# MAINSSMB_V1_2.net
KiCad netlist of a schematic drawn in Altium Designer
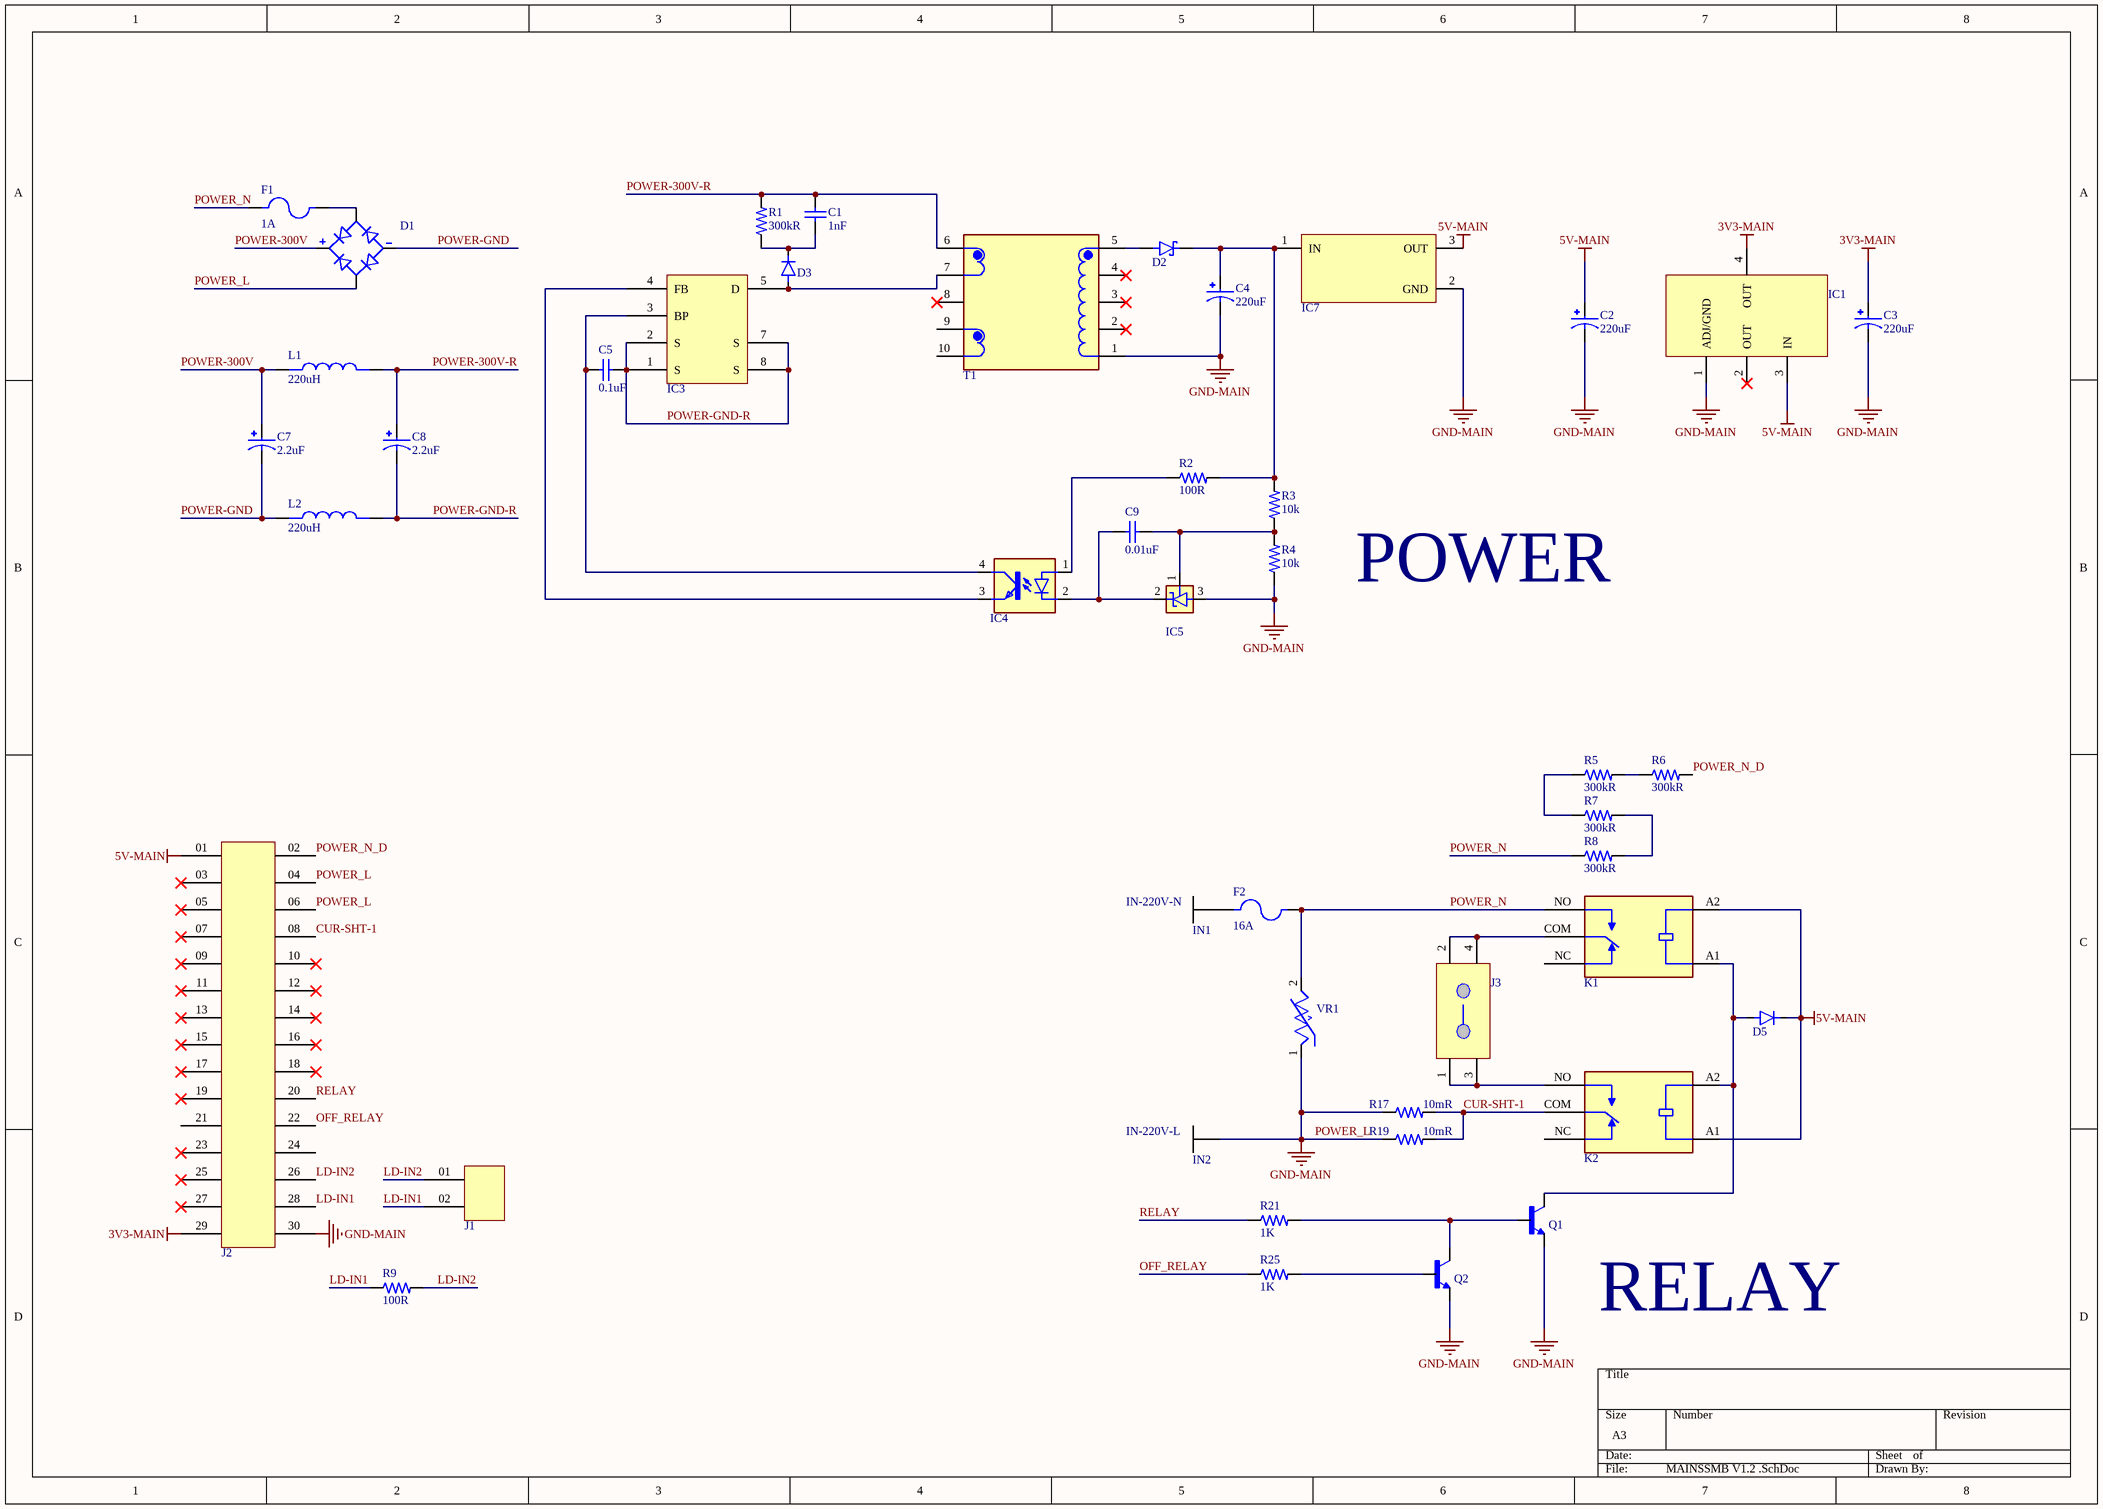
[diagram p0: MAINSSMB V1.2 .SchDoc]

(export (version "E")
  (design (tool "Eeschema 10.0.6"))
  (components
    (comp (ref "C1")
      (value "1nF")
      (footprint "TH-CAP-HxLxW-5.5x4.0x2.5-TDKC")
      (description "Capacitor Ceramic 0.001uF 50V C0G 5% 5mm T/R")
      (fields
        (field (name "MANUFACTURER") "TDK")
        (field (name "MANUFACTURER PART NUMBER") "FA28NP01H102JNU06")
        (field (name "DESIGNER") "TVBac")
      )
      (libsource (lib "Capacitors") (part "CAP; TH; 0.001uF; 50V; FA28NP01H102JNU06"))
    )
    (comp (ref "C2")
      (value "220uF")
      (footprint "SMD-DxLxW-6.3x6.6x6.6-PEC")
      (description "Cap Aluminum Polymer 220uF 16VDC 20% (6.3 X 5.9mm) SMD 0.022 Ohm 1040mA 1000h 125C T/R")
      (fields
        (field (name "MANUFACTURER") "Panasonic")
        (field (name "MANUFACTURER PART NUMBER") "16SVPK220M")
        (field (name "DESIGNER") "TVBac")
      )
      (libsource (lib "Capacitors") (part "CAP; 220uF; 16V; SMD; 16SVPK220M"))
    )
    (comp (ref "C3")
      (value "220uF")
      (footprint "SMD-DxLxW-6.3x6.6x6.6-PEC")
      (description "Cap Aluminum Polymer 220uF 10VDC 20%( 6.3 X 5.9mm) SMD 0.02 Ohm 2700mA 2000h 105C T/R")
      (fields
        (field (name "MANUFACTURER") "Panasonic")
        (field (name "MANUFACTURER PART NUMBER") "10SVPE220M")
        (field (name "DESIGNER") "TVBac")
      )
      (libsource (lib "Capacitors") (part "CAP; 220uF; 10V; SMD; 10SVPE220M"))
    )
    (comp (ref "C4")
      (value "220uF")
      (footprint "SMD-DxLxW-6.3x6.6x6.6-PEC")
      (description "Cap Aluminum Polymer 220uF 16VDC 20% (6.3 X 5.9mm) SMD 0.022 Ohm 1040mA 1000h 125C T/R")
      (fields
        (field (name "MANUFACTURER") "Panasonic")
        (field (name "MANUFACTURER PART NUMBER") "16SVPK220M")
        (field (name "DESIGNER") "TVBac")
      )
      (libsource (lib "Capacitors") (part "CAP; 220uF; 16V; SMD; 16SVPK220M"))
    )
    (comp (ref "C5")
      (value "0.1uF")
      (footprint "SMD-CAP-0603-YAGEO")
      (description "Multilayer Ceramic Capacitor, 0.1 uF, 50 V, ï¿½ 5%, X7R, 0603 [1608 Metric]")
      (fields
        (field (name "MANUFACTURER") "Yageo")
        (field (name "MANUFACTURER PART NUMBER") "CC0603JRX7R9BB104")
        (field (name "DESIGNER") "TVBac")
      )
      (libsource (lib "Capacitors") (part "CAP; 0.1uF; 50V; 0603; SMD; CC0603JRX7R9BB104"))
    )
    (comp (ref "C7")
      (value "2.2uF")
      (footprint "TH-CAP-HxD-12.5x8.0-PEC")
      (description "Cap Aluminum Lytic 2.2uF 400V 20% (8 X 11.5mm) Radial 3.5mm 50mA 2000h 85C Automotive Bulk")
      (fields
        (field (name "MANUFACTURER") "Panasonic")
        (field (name "MANUFACTURER PART NUMBER") "ECA-2GM2R2")
        (field (name "DESIGNER") "TVBac")
      )
      (libsource (lib "Capacitors") (part "CAP; TH; 2.2uF; 400V; ECA-2GM2R2"))
    )
    (comp (ref "C8")
      (value "2.2uF")
      (footprint "TH-CAP-HxD-12.5x8.0-PEC")
      (description "Cap Aluminum Lytic 2.2uF 400V 20% (8 X 11.5mm) Radial 3.5mm 50mA 2000h 85C Automotive Bulk")
      (fields
        (field (name "MANUFACTURER") "Panasonic")
        (field (name "MANUFACTURER PART NUMBER") "ECA-2GM2R2")
        (field (name "DESIGNER") "TVBac")
      )
      (libsource (lib "Capacitors") (part "CAP; TH; 2.2uF; 400V; ECA-2GM2R2"))
    )
    (comp (ref "C9")
      (value "0.01uF")
      (footprint "SMD-CAP-0603-YAGEO")
      (description "Surface Mount Ceramic Multilayer Capacitor 0.01uF 5% X7R 25V 0603 Paper T/R")
      (fields
        (field (name "MANUFACTURER") "Yageo")
        (field (name "MANUFACTURER PART NUMBER") "CC0603JRX7R8BB103")
        (field (name "DESIGNER") "TVBac")
      )
      (libsource (lib "Capacitors") (part "CAP; 0.01uF; 25V; 0603; SMD; CC0603JRX7R8BB103"))
    )
    (comp (ref "D1")
      (value "Bridge Rectifier Single Phase Standard 1 kV Surface Mount ABS")
      (footprint "DIODE-SMD-4-TSC")
      (description "Bridge Rectifiers 1A, 1000V, Standard Bridge Rectifier")
      (fields
        (field (name "MANUFACTURER") "Taiwan Semiconductor")
        (field (name "MANUFACTURER PART NUMBER") "ABS10H")
        (field (name "DESIGNER") "TVBac")
      )
      (libsource (lib "Diode") (part "DIODE; SMD; ABS10H"))
    )
    (comp (ref "D2")
      (value "Diode 40 V 3A Surface Mount DO-214AC (SMA)")
      (footprint "SMD-DO-214AC-214-CT")
      (description "Diode Schottky Si 40V 3A 2-Pin SMA T/R")
      (fields
        (field (name "MANUFACTURER") "Comchip")
        (field (name "MANUFACTURER PART NUMBER") "SS34-HF")
        (field (name "DESIGNER") "TVBac")
      )
      (libsource (lib "Smartsocket") (part "DIODE; SMD; SCHOTTKY; SS34-HF"))
    )
    (comp (ref "D3")
      (value "Diode 1000 V 1A Surface Mount SOD-123FL")
      (footprint "SOD-123FL-SMCDS")
      (description "Diode Gen Purp 1KV 1A SOD123FL")
      (fields
        (field (name "MANUFACTURER") "Sangdest Microelectronics")
        (field (name "MANUFACTURER PART NUMBER") "1N4007FL")
        (field (name "DESIGNER") "TVBac")
      )
      (libsource (lib "Diode") (part "DIODE; SMD; 1N4007FLN4007;"))
    )
    (comp (ref "D5")
      (value "Diode 1000 V 1A Surface Mount SOD-123FL")
      (footprint "SOD-123FL-SMCDS")
      (description "Diode Gen Purp 1KV 1A SOD123FL")
      (fields
        (field (name "MANUFACTURER") "Sangdest Microelectronics")
        (field (name "MANUFACTURER PART NUMBER") "1N4007FL")
        (field (name "DESIGNER") "TVBac")
      )
      (libsource (lib "Diode") (part "DIODE; SMD; 1N4007FLN4007;"))
    )
    (comp (ref "F1")
      (value "1A")
      (footprint "FUSE-HxLxW-8.0x8.5x4.0-LI")
      (description "Fuse Subminiature Slow Blow Acting 1A 300V Radial 8.5 X 4 X 8mm Ammo Pack")
      (fields
        (field (name "MANUFACTURER") "Littelfuse Wickmann")
        (field (name "MANUFACTURER PART NUMBER") "36911000000")
        (field (name "DESIGNER") "TVBac")
      )
      (libsource (lib "Smartsocket") (part "FUSE; 1A; 36911000000"))
    )
    (comp (ref "F2")
      (value "16A")
      (footprint "FUSE-3.6mmx10mm-AXIAL")
      (fields
        (field (name "MANUFACTURER") "Schurter")
        (field (name "MANUFACTURER PART NUMBER") "0031.8211")
        (field (name "Comment") "FUSE; 16A; 0031.8211_1")
        (field (name "DESIGNER") "TVBac")
      )
      (libsource (lib "Socket") (part "FUSE; 16A; 0031.8211_1"))
    )
    (comp (ref "IC1")
      (value "Linear Voltage Regulator IC Positive Fixed 1 Output 1A SOT-223-3")
      (footprint "IC:SOT-223-3-DI")
      (description "Linear Voltage Regulator IC 1 Output 1A SOT-223")
      (fields
        (field (name "MF") "Diodes Inc.")
        (field (name "MP") "AZ1117EH-3.3TRG1")
        (field (name "DESIGNER") "TVBac")
      )
      (libsource (lib "IC") (part "LDO; 3V3; 1A; SMD; AZ1117EH-3.3TRG1"))
    )
    (comp (ref "IC3")
      (value "Converter Offline Flyback Topology 132kHz SMD-8B")
      (footprint "SMD-8B-PI")
      (description "AC to DC Switching Converter Off-Line Switcher 140kHz 7-Pin SMD-B / IC OFFLINE SWIT HV 8SMD")
      (fields
        (field (name "MANUFACTURER") "Power Integrations")
        (field (name "MANUFACTURER PART NUMBER") "LNK364GN-TL")
        (field (name "DESIGNER") "TVBac")
      )
      (libsource (lib "Smartsocket") (part "LNK364GN-TL"))
    )
    (comp (ref "IC4")
      (value "Optoisolator Transistor Output 3750Vrms 1 Channel 4-SOP (2.54mm)")
      (footprint "SOP-4")
      (description "Transistor Output Optocoupler, 1-Element, 3750V Isolation")
      (fields (field (name "MANUFACTURER") "Everlight") (field (name "MANUFACTURER PART NUMBER") "EL357N-G"))
      (libsource (lib "IC") (part "ISO; 1CH; EL357N-G"))
    )
    (comp (ref "IC5")
      (value "Shunt Voltage Reference IC Adjustable 2.495V 36 VV ±1% 100 mA SOT-23-3")
      (footprint "SOT-23-3-DS")
      (description "V-Ref Adjustable 2.495V to 36V 100mA Automotive 3-Pin SOT-23 T/R")
      (fields
        (field (name "MANUFACTURER") "Texas Instruments")
        (field (name "MANUFACTURER PART NUMBER") "TL431AIDBZR")
        (field (name "DESIGNER") "TVBac")
      )
      (libsource (lib "IC") (part "TL431AIDBZR; MIRROID;"))
    )
    (comp (ref "IC7")
      (value "Linear Voltage Regulator IC Positive Fixed 1 Output 1A TO-252")
      (footprint "TO252-3-RS")
      (description "Linear Voltage Regulator, Fixed, Positive Output, 7.5 V to 25 V, 5V, 1A, 3 Pins, TO-252 (DPAK)")
      (fields
        (field (name "MANUFACTURER") "Rohm")
        (field (name "MANUFACTURER PART NUMBER") "BA17805FP-E2")
        (field (name "DESIGNER") "TVBac")
      )
      (libsource (lib "IC") (part "LDO; 5V; 1A; BA17805FP-E2"))
    )
    (comp (ref "IN1")
      (value "INPUT")
      (footprint "INPUT-2.0x3.5")
      (fields (field (name "DESIGNER") "TVBac"))
      (libsource (lib "Socket") (part "INPUT-2.0x3.5"))
    )
    (comp (ref "IN2")
      (value "INPUT")
      (footprint "INPUT-2.0x3.5")
      (fields (field (name "DESIGNER") "TVBac"))
      (libsource (lib "Socket") (part "INPUT-2.0x3.5"))
    )
    (comp (ref "J1")
      (value "Connector Header Through Hole 2 position")
      (footprint "HEADER-2.54-2")
      (description "Headers & Wire Housings Classic PCB Header Strips, 0.100 pitch")
      (fields
        (field (name "MANUFACTURER") "Samtec")
        (field (name "MANUFACTURER PART NUMBER") "TSW-101-15-T-D")
        (field (name "DESIGNER") "TVBac")
      )
      (libsource (lib "Socket") (part "HEADER; 2PIN; 2.54; VER; TSW-101-15-T-D"))
    )
    (comp (ref "J2")
      (value "30 Position Elevated Socket Connector 0.100\" (2.54mm) Through Hole Gold")
      (footprint "HEADER-2.54-15x2-HOR-SAM - N3D")
      (description "Connector Receptacle 30 Position 0.100\" (2.54mm) Gold Through Hole")
      (fields
        (field (name "MANUFACTURER") "Samtec")
        (field (name "MANUFACTURER PART NUMBER") "ESQ-115-12-G-D")
        (field (name "DESIGNER") "TVBac")
      )
      (libsource (lib "Socket") (part "HEADER; 15x2PIN; 2.54; VER; ESQ-115-12-G-D; N3D"))
    )
    (comp (ref "J3")
      (value "Connector Header Through Hole 4 position 0.100\" (2.54mm)")
      (footprint "SOCKET-SINGLE-WEV1081H")
      (description "Conn Unshrouded Header HDR 4 POS 2.54mm Solder ST Thru-Hole Automotive Bulk")
      (fields
        (field (name "MANUFACTURER") "Samtec")
        (field (name "MANUFACTURER PART NUMBER") "TSW-104-14-L-S")
        (field (name "DESIGNER") "TVBac")
      )
      (libsource (lib "Socket") (part "SOCKET; SINGLE;"))
    )
    (comp (ref "K1")
      (value "JQ1P-5V-F")
      (footprint "RELAY-JQ1P-10A-HxLxW-15.6x20.5x10.0-PEW")
      (description "RELAY GEN PURPOSE SPDT 10A 5V")
      (fields (field (name "DESIGNER") "TVBac"))
      (libsource (lib "Relay") (part "RELAY; SINGLE; 5VDC; CMP-05607-000163-1"))
    )
    (comp (ref "K2")
      (value "JQ1P-5V-F")
      (footprint "RELAY-JQ1P-10A-HxLxW-15.6x20.5x10.0-PEW")
      (description "RELAY GEN PURPOSE SPDT 10A 5V")
      (fields (field (name "DESIGNER") "TVBac"))
      (libsource (lib "Relay") (part "RELAY; SINGLE; 5VDC; CMP-05607-000163-1"))
    )
    (comp (ref "L1")
      (value "220uH")
      (footprint "SMD-HxLxW-1.8x4.0x4.0-ALLC")
      (description "Power Inductor (SMD), 220 uH, ± 20%, 250 mA, Shielded, 330 mA, 4mm x 4mm x 1.8mm")
      (fields
        (field (name "MANUFACTURER") "Abracon")
        (field (name "MANUFACTURER PART NUMBER") "ASPI-0418FS-221M-T3")
        (field (name "DESIGNER") "TVBac")
      )
      (libsource (lib "Inductors") (part "IND; 220uH; 250mA; ASPI-0418FS-221M-T3"))
    )
    (comp (ref "L2")
      (value "220uH")
      (footprint "SMD-HxLxW-1.8x4.0x4.0-ALLC")
      (description "Power Inductor (SMD), 220 uH, ± 20%, 250 mA, Shielded, 330 mA, 4mm x 4mm x 1.8mm")
      (fields
        (field (name "MANUFACTURER") "Abracon")
        (field (name "MANUFACTURER PART NUMBER") "ASPI-0418FS-221M-T3")
        (field (name "DESIGNER") "TVBac")
      )
      (libsource (lib "Inductors") (part "IND; 220uH; 250mA; ASPI-0418FS-221M-T3"))
    )
    (comp (ref "Q1")
      (value "Bipolar (BJT) Transistor NPN 45 V 500 mA 100MHz 300 mW Surface Mount SOT-23-3 (TO-236)")
      (footprint "SOT-23-3-ONSEMI")
      (description "Single Bipolar Transistor, NPN, 45 V, 500 mA, 225 mW, SOT-23 (TO-236), 3 Pins, Surface Mount")
      (fields
        (field (name "MANUFACTURER") "ON Semiconductor")
        (field (name "MANUFACTURER PART NUMBER") "BC817-25LT1G")
        (field (name "DESIGNER") "TVBac")
      )
      (libsource (lib "Transistors") (part "TRAN; NPN; 500mA;V;  BC817-25LT1G"))
    )
    (comp (ref "Q2")
      (value "Bipolar (BJT) Transistor NPN 45 V 500 mA 100MHz 300 mW Surface Mount SOT-23-3 (TO-236)")
      (footprint "SOT-23-3-ONSEMI")
      (description "Single Bipolar Transistor, NPN, 45 V, 500 mA, 225 mW, SOT-23 (TO-236), 3 Pins, Surface Mount")
      (fields
        (field (name "MANUFACTURER") "ON Semiconductor")
        (field (name "MANUFACTURER PART NUMBER") "BC817-25LT1G")
        (field (name "DESIGNER") "TVBac")
      )
      (libsource (lib "Transistors") (part "TRAN; NPN; 500mA;V;  BC817-25LT1G"))
    )
    (comp (ref "R1")
      (value "300kR")
      (footprint "SMD-RES-1206-RS")
      (description "Res Thick Film 1206 300K Ohm 1% 0.5W(1/2W) ±100ppm/C Epoxy Resin Pad SMD Automotive T/R")
      (fields
        (field (name "MANUFACTURER") "Rohm")
        (field (name "MANUFACTURER PART NUMBER") "ESR18EZPF3003")
        (field (name "DESIGNER") "TVBac")
      )
      (libsource (lib "Resistors") (part "RES; 300K; 1206; ESR18EZPF3003"))
    )
    (comp (ref "R2")
      (value "100R")
      (footprint "SMD-RES-0603-RS")
      (description "Res Thick Film 0603 100 Ohm 1% 0.1W(1/10W) ±100ppm/C Pad SMD T/R Automotive AEC-Q200")
      (fields
        (field (name "MANUFACTURER") "Rohm")
        (field (name "MANUFACTURER PART NUMBER") "KTR03EZPF1000")
        (field (name "DESIGNER") "TVBac")
      )
      (libsource (lib "Resistors") (part "RES; 100R; 0603; SMD; KTR03EZPF1000"))
    )
    (comp (ref "R3")
      (value "10k")
      (footprint "SMD-RES-0603-SEI")
      (description "SMD Chip Resistor, 10 kOhm, ± 1%, 250 mW, 0603 [1608 Metric], Thick Film, Anti-Surge")
      (fields
        (field (name "MANUFACTURER") "Rohm")
        (field (name "MANUFACTURER PART NUMBER") "ESR03EZPF1002")
        (field (name "DESIGNER") "TVBac")
      )
      (libsource (lib "Resistors") (part "RES; 10K; 0603; SMD; ESR03EZPF1002"))
    )
    (comp (ref "R4")
      (value "10k")
      (footprint "SMD-RES-0603-SEI")
      (description "SMD Chip Resistor, 10 kOhm, ± 1%, 250 mW, 0603 [1608 Metric], Thick Film, Anti-Surge")
      (fields
        (field (name "MANUFACTURER") "Rohm")
        (field (name "MANUFACTURER PART NUMBER") "ESR03EZPF1002")
        (field (name "DESIGNER") "TVBac")
      )
      (libsource (lib "Resistors") (part "RES; 10K; 0603; SMD; ESR03EZPF1002"))
    )
    (comp (ref "R5")
      (value "300kR")
      (footprint "SMD-RES-0603-RS")
      (description "Res High Voltage Thick Film 0603 300k Ohm 1% 1/10W ±100ppm/°C Molded Paper T/R")
      (fields
        (field (name "MANUFACTURER") "Rohm")
        (field (name "MANUFACTURER PART NUMBER") "KTR03EZPF3003")
        (field (name "DESIGNER") "TVBac")
      )
      (libsource (lib "Resistors") (part "RES; 300K; 0603; SMD; KTR03EZPF3003"))
    )
    (comp (ref "R6")
      (value "300kR")
      (footprint "SMD-RES-0603-RS")
      (description "Res High Voltage Thick Film 0603 300k Ohm 1% 1/10W ±100ppm/°C Molded Paper T/R")
      (fields
        (field (name "MANUFACTURER") "Rohm")
        (field (name "MANUFACTURER PART NUMBER") "KTR03EZPF3003")
        (field (name "DESIGNER") "TVBac")
      )
      (libsource (lib "Resistors") (part "RES; 300K; 0603; SMD; KTR03EZPF3003"))
    )
    (comp (ref "R7")
      (value "300kR")
      (footprint "SMD-RES-0603-RS")
      (description "Res High Voltage Thick Film 0603 300k Ohm 1% 1/10W ±100ppm/°C Molded Paper T/R")
      (fields
        (field (name "MANUFACTURER") "Rohm")
        (field (name "MANUFACTURER PART NUMBER") "KTR03EZPF3003")
        (field (name "DESIGNER") "TVBac")
      )
      (libsource (lib "Resistors") (part "RES; 300K; 0603; SMD; KTR03EZPF3003"))
    )
    (comp (ref "R8")
      (value "300kR")
      (footprint "SMD-RES-0603-RS")
      (description "Res High Voltage Thick Film 0603 300k Ohm 1% 1/10W ±100ppm/°C Molded Paper T/R")
      (fields
        (field (name "MANUFACTURER") "Rohm")
        (field (name "MANUFACTURER PART NUMBER") "KTR03EZPF3003")
        (field (name "DESIGNER") "TVBac")
      )
      (libsource (lib "Resistors") (part "RES; 300K; 0603; SMD; KTR03EZPF3003"))
    )
    (comp (ref "R9")
      (value "100R")
      (footprint "SMD-RES-0603-RS")
      (description "Res Thick Film 0603 100 Ohm 1% 0.1W(1/10W) ±100ppm/C Pad SMD T/R Automotive AEC-Q200")
      (fields
        (field (name "MANUFACTURER") "Rohm")
        (field (name "MANUFACTURER PART NUMBER") "KTR03EZPF1000")
        (field (name "DESIGNER") "TVBac")
      )
      (libsource (lib "Resistors") (part "RES; 100R; 0603; SMD; KTR03EZPF1000"))
    )
    (comp (ref "R17")
      (value "10mR")
      (footprint "SMD-RES-2512-VD")
      (description "Res Current Sense Metal Plate 2512 0.01 Ohm 1% 3W ±110ppm/°C Molded T/R")
      (fields
        (field (name "MANUFACTURER") "Vishay")
        (field (name "MANUFACTURER PART NUMBER") "WFMA2512R0100FEA")
        (field (name "DESIGNER") "TVBac")
      )
      (libsource (lib "Smartsocket") (part "RES; SHUNT; 10mOhm; SMD; WFMA2512R0100FEA"))
    )
    (comp (ref "R19")
      (value "10mR")
      (footprint "SMD-RES-2512-VD")
      (description "Res Current Sense Metal Plate 2512 0.01 Ohm 1% 3W ±110ppm/°C Molded T/R")
      (fields
        (field (name "MANUFACTURER") "Vishay")
        (field (name "MANUFACTURER PART NUMBER") "WFMA2512R0100FEA")
        (field (name "DESIGNER") "TVBac")
      )
      (libsource (lib "Smartsocket") (part "RES; SHUNT; 10mOhm; SMD; WFMA2512R0100FEA"))
    )
    (comp (ref "R21")
      (value "1K")
      (footprint "SMD-RES-0603-SEI")
      (description "SMD Chip Resistor, 1 kOhm, ± 1%, 250 mW, 0603 [1608 Metric], Thick Film, Anti-Surge")
      (fields
        (field (name "MANUFACTURER") "Rohm")
        (field (name "MANUFACTURER PART NUMBER") "ESR03EZPF1001")
        (field (name "DESIGNER") "TVBac")
      )
      (libsource (lib "Smartsocket") (part "RES; 1K; 0603; SMD; ESR03EZPF1001"))
    )
    (comp (ref "R25")
      (value "1K")
      (footprint "SMD-RES-0603-SEI")
      (description "SMD Chip Resistor, 1 kOhm, ± 1%, 250 mW, 0603 [1608 Metric], Thick Film, Anti-Surge")
      (fields
        (field (name "MANUFACTURER") "Rohm")
        (field (name "MANUFACTURER PART NUMBER") "ESR03EZPF1001")
        (field (name "DESIGNER") "TVBac")
      )
      (libsource (lib "Smartsocket") (part "RES; 1K; 0603; SMD; ESR03EZPF1001"))
    )
    (comp (ref "T1")
      (value "For SMPS Transformer 500VAC Isolation Through Hole")
      (footprint "EE13 - POWER")
      (description "OFFLINE TRANSFORMER 6W EE13/7/6")
      (fields (field (name "MF") "Wurth Electronics Inc") (field (name "MP") "EE13/6/6"))
      (libsource (lib "Transformer") (part "EE13/6/6-Power"))
    )
    (comp (ref "VR1")
      (value "VAR; B72214S0271K101")
      (footprint "VARISTOR-TDK")
      (description "Var MOV 275VAC/350VDC 4500A 430V Thru-Hole Radial Automotive Bulk")
      (fields
        (field (name "MANUFACTURER") "TDK EPCOS")
        (field (name "MANUFACTURER PART NUMBER") "B72214S0271K101")
      )
      (libsource (lib "Capacitors") (part "VAR; B72214S0271K101"))
    )
  )
  (nets
    (net (code "1") (name "/CUR-SHT-1") (class "Default")
      (node (ref "J2") (pin "08") (pinfunction "08_08") (pintype "passive"))
      (node (ref "K2") (pin "COM") (pinfunction "COM_COM") (pintype "passive"))
      (node (ref "R17") (pin "2") (pinfunction "2_2") (pintype "passive"))
      (node (ref "R19") (pin "2") (pinfunction "2_2") (pintype "passive"))
    )
    (net (code "2") (name "/LD-IN1") (class "Default")
      (node (ref "J1") (pin "02") (pinfunction "2_02") (pintype "passive"))
      (node (ref "J2") (pin "28") (pinfunction "28_28") (pintype "passive"))
      (node (ref "R9") (pin "1") (pinfunction "1_1") (pintype "passive"))
    )
    (net (code "3") (name "/LD-IN2") (class "Default")
      (node (ref "J1") (pin "01") (pinfunction "1_01") (pintype "passive"))
      (node (ref "J2") (pin "26") (pinfunction "26_26") (pintype "passive"))
      (node (ref "R9") (pin "2") (pinfunction "2_2") (pintype "passive"))
    )
    (net (code "4") (name "/OFF_RELAY") (class "Default")
      (node (ref "J2") (pin "22") (pinfunction "22_22") (pintype "passive"))
      (node (ref "R25") (pin "1") (pinfunction "1_1") (pintype "passive"))
    )
    (net (code "5") (name "/POWER-300V") (class "Default")
      (node (ref "C7") (pin "1") (pinfunction "1_1") (pintype "passive"))
      (node (ref "D1") (pin "POS") (pinfunction "POS_POS") (pintype "passive"))
      (node (ref "L1") (pin "1") (pinfunction "1_1") (pintype "passive"))
    )
    (net (code "6") (name "/POWER-300V-R") (class "Default")
      (node (ref "C1") (pin "2") (pinfunction "2_2") (pintype "passive"))
      (node (ref "C8") (pin "1") (pinfunction "1_1") (pintype "passive"))
      (node (ref "L1") (pin "2") (pinfunction "2_2") (pintype "passive"))
      (node (ref "R1") (pin "2") (pinfunction "2_2") (pintype "passive"))
      (node (ref "T1") (pin "6") (pinfunction "6_6") (pintype "passive"))
    )
    (net (code "7") (name "/POWER-GND") (class "Default")
      (node (ref "C7") (pin "2") (pinfunction "2_2") (pintype "passive"))
      (node (ref "D1") (pin "NEG") (pinfunction "NEG_NEG") (pintype "passive"))
      (node (ref "L2") (pin "1") (pinfunction "1_1") (pintype "passive"))
    )
    (net (code "8") (name "/POWER-GND-R") (class "Default")
      (node (ref "C5") (pin "2") (pinfunction "2_2") (pintype "passive"))
      (node (ref "C8") (pin "2") (pinfunction "2_2") (pintype "passive"))
      (node (ref "IC3") (pin "1") (pinfunction "S_1") (pintype "passive"))
      (node (ref "IC3") (pin "2") (pinfunction "S_2") (pintype "passive"))
      (node (ref "IC3") (pin "7") (pinfunction "S_7") (pintype "passive"))
      (node (ref "IC3") (pin "8") (pinfunction "S_8") (pintype "passive"))
      (node (ref "L2") (pin "2") (pinfunction "2_2") (pintype "passive"))
    )
    (net (code "9") (name "/POWER_N") (class "Default")
      (node (ref "F1") (pin "1") (pinfunction "1_1") (pintype "passive"))
      (node (ref "F2") (pin "2") (pinfunction "2_2") (pintype "passive"))
      (node (ref "K1") (pin "NO") (pinfunction "NO_NO") (pintype "passive"))
      (node (ref "R8") (pin "1") (pinfunction "1_1") (pintype "passive"))
      (node (ref "VR1") (pin "2") (pinfunction "2_2") (pintype "passive"))
    )
    (net (code "10") (name "/POWER_N_D") (class "Default")
      (node (ref "J2") (pin "02") (pinfunction "02_02") (pintype "passive"))
      (node (ref "R6") (pin "2") (pinfunction "2_2") (pintype "passive"))
    )
    (net (code "11") (name "/RELAY") (class "Default")
      (node (ref "J2") (pin "20") (pinfunction "20_20") (pintype "passive"))
      (node (ref "R21") (pin "1") (pinfunction "1_1") (pintype "passive"))
    )
    (net (code "12") (name "3V3-MAIN") (class "Default")
      (node (ref "C3") (pin "1") (pinfunction "1_1") (pintype "passive"))
      (node (ref "IC1") (pin "4") (pinfunction "OUT_4") (pintype "passive"))
      (node (ref "J2") (pin "29") (pinfunction "29_29") (pintype "passive"))
    )
    (net (code "13") (name "5V-MAIN") (class "Default")
      (node (ref "C2") (pin "1") (pinfunction "1_1") (pintype "passive"))
      (node (ref "D5") (pin "K") (pinfunction "K_K") (pintype "passive"))
      (node (ref "IC1") (pin "3") (pinfunction "IN_3") (pintype "passive"))
      (node (ref "IC7") (pin "3") (pinfunction "OUT_3") (pintype "passive"))
      (node (ref "J2") (pin "01") (pinfunction "01_01") (pintype "passive"))
      (node (ref "K1") (pin "A2") (pinfunction "A2_A2") (pintype "passive"))
      (node (ref "K2") (pin "A1") (pinfunction "A1_A1") (pintype "passive"))
    )
    (net (code "14") (name "GND-MAIN") (class "Default")
      (node (ref "C2") (pin "2") (pinfunction "2_2") (pintype "passive"))
      (node (ref "C3") (pin "2") (pinfunction "2_2") (pintype "passive"))
      (node (ref "C4") (pin "2") (pinfunction "2_2") (pintype "passive"))
      (node (ref "D1") (pin "AC2") (pinfunction "AC2_AC2") (pintype "passive"))
      (node (ref "IC1") (pin "1") (pinfunction "ADJ/GND_1") (pintype "passive"))
      (node (ref "IC5") (pin "3") (pinfunction "ANODE_3") (pintype "passive"))
      (node (ref "IC7") (pin "2") (pinfunction "GND_2") (pintype "passive"))
      (node (ref "IN2") (pin "1") (pinfunction "IN_1") (pintype "passive"))
      (node (ref "J2") (pin "04") (pinfunction "04_04") (pintype "passive"))
      (node (ref "J2") (pin "06") (pinfunction "06_06") (pintype "passive"))
      (node (ref "J2") (pin "30") (pinfunction "30_30") (pintype "passive"))
      (node (ref "Q1") (pin "2") (pinfunction "E_2") (pintype "passive"))
      (node (ref "Q2") (pin "2") (pinfunction "E_2") (pintype "passive"))
      (node (ref "R17") (pin "1") (pinfunction "1_1") (pintype "passive"))
      (node (ref "R19") (pin "1") (pinfunction "1_1") (pintype "passive"))
      (node (ref "R4") (pin "1") (pinfunction "1_1") (pintype "passive"))
      (node (ref "T1") (pin "1") (pinfunction "1_1") (pintype "passive"))
      (node (ref "VR1") (pin "1") (pinfunction "1_1") (pintype "passive"))
    )
    (net (code "15") (name "Net-(C1-Pad1)") (class "Default")
      (node (ref "C1") (pin "1") (pinfunction "1_1") (pintype "passive"))
      (node (ref "D3") (pin "K") (pinfunction "K_K") (pintype "passive"))
      (node (ref "R1") (pin "1") (pinfunction "1_1") (pintype "passive"))
    )
    (net (code "16") (name "Net-(D1-PadAC1)") (class "Default")
      (node (ref "D1") (pin "AC1") (pinfunction "AC1_AC1") (pintype "passive"))
      (node (ref "F1") (pin "2") (pinfunction "2_2") (pintype "passive"))
    )
    (net (code "17") (name "Net-(D2-A)") (class "Default")
      (node (ref "D2") (pin "2") (pinfunction "A_2") (pintype "passive"))
      (node (ref "T1") (pin "5") (pinfunction "5_5") (pintype "passive"))
    )
    (net (code "18") (name "Net-(D2-K)") (class "Default")
      (node (ref "C4") (pin "1") (pinfunction "1_1") (pintype "passive"))
      (node (ref "D2") (pin "1") (pinfunction "K_1") (pintype "passive"))
      (node (ref "IC7") (pin "1") (pinfunction "IN_1") (pintype "passive"))
      (node (ref "R2") (pin "2") (pinfunction "2_2") (pintype "passive"))
      (node (ref "R3") (pin "2") (pinfunction "2_2") (pintype "passive"))
    )
    (net (code "19") (name "Net-(IC3-BP)") (class "Default")
      (node (ref "C5") (pin "1") (pinfunction "1_1") (pintype "passive"))
      (node (ref "IC3") (pin "3") (pinfunction "BP_3") (pintype "passive"))
      (node (ref "IC4") (pin "4") (pinfunction "COL_4") (pintype "passive"))
    )
    (net (code "20") (name "Net-(IC3-D)") (class "Default")
      (node (ref "D3") (pin "A") (pinfunction "A_A") (pintype "passive"))
      (node (ref "IC3") (pin "5") (pinfunction "D_5") (pintype "passive"))
      (node (ref "T1") (pin "7") (pinfunction "7_7") (pintype "passive"))
    )
    (net (code "21") (name "Net-(IC3-FB)") (class "Default")
      (node (ref "IC3") (pin "4") (pinfunction "FB_4") (pintype "passive"))
      (node (ref "IC4") (pin "3") (pinfunction "EMIT_3") (pintype "passive"))
    )
    (net (code "22") (name "Net-(IC4-A)") (class "Default")
      (node (ref "IC4") (pin "1") (pinfunction "A_1") (pintype "passive"))
      (node (ref "R2") (pin "1") (pinfunction "1_1") (pintype "passive"))
    )
    (net (code "23") (name "Net-(IC4-C)") (class "Default")
      (node (ref "C9") (pin "1") (pinfunction "1_1") (pintype "passive"))
      (node (ref "IC4") (pin "2") (pinfunction "C_2") (pintype "passive"))
      (node (ref "IC5") (pin "2") (pinfunction "CATHODE_2") (pintype "passive"))
    )
    (net (code "24") (name "Net-(IC5-REF)") (class "Default")
      (node (ref "C9") (pin "2") (pinfunction "2_2") (pintype "passive"))
      (node (ref "IC5") (pin "1") (pinfunction "REF_1") (pintype "passive"))
      (node (ref "R3") (pin "1") (pinfunction "1_1") (pintype "passive"))
      (node (ref "R4") (pin "2") (pinfunction "2_2") (pintype "passive"))
    )
    (net (code "25") (name "Net-(IN1-IN)") (class "Default")
      (node (ref "F2") (pin "1") (pinfunction "1_1") (pintype "passive"))
      (node (ref "IN1") (pin "1") (pinfunction "IN_1") (pintype "passive"))
    )
    (net (code "26") (name "Net-(J3-Pad1)") (class "Default")
      (node (ref "J3") (pin "1") (pinfunction "1_1") (pintype "passive"))
      (node (ref "J3") (pin "3") (pinfunction "3_3") (pintype "passive"))
      (node (ref "K2") (pin "NO") (pinfunction "NO_NO") (pintype "passive"))
    )
    (net (code "27") (name "Net-(J3-Pad2)") (class "Default")
      (node (ref "J3") (pin "2") (pinfunction "2_2") (pintype "passive"))
      (node (ref "J3") (pin "4") (pinfunction "4_4") (pintype "passive"))
      (node (ref "K1") (pin "COM") (pinfunction "COM_COM") (pintype "passive"))
    )
    (net (code "28") (name "Net-(Q1-B)") (class "Default")
      (node (ref "Q1") (pin "1") (pinfunction "B_1") (pintype "passive"))
      (node (ref "Q2") (pin "3") (pinfunction "C_3") (pintype "passive"))
      (node (ref "R21") (pin "2") (pinfunction "2_2") (pintype "passive"))
    )
    (net (code "29") (name "Net-(Q1-C)") (class "Default")
      (node (ref "D5") (pin "A") (pinfunction "A_A") (pintype "passive"))
      (node (ref "K1") (pin "A1") (pinfunction "A1_A1") (pintype "passive"))
      (node (ref "K2") (pin "A2") (pinfunction "A2_A2") (pintype "passive"))
      (node (ref "Q1") (pin "3") (pinfunction "C_3") (pintype "passive"))
    )
    (net (code "30") (name "Net-(Q2-B)") (class "Default")
      (node (ref "Q2") (pin "1") (pinfunction "B_1") (pintype "passive"))
      (node (ref "R25") (pin "2") (pinfunction "2_2") (pintype "passive"))
    )
    (net (code "31") (name "Net-(R5-Pad1)") (class "Default")
      (node (ref "R5") (pin "1") (pinfunction "1_1") (pintype "passive"))
      (node (ref "R7") (pin "1") (pinfunction "1_1") (pintype "passive"))
    )
    (net (code "32") (name "Net-(R5-Pad2)") (class "Default")
      (node (ref "R5") (pin "2") (pinfunction "2_2") (pintype "passive"))
      (node (ref "R6") (pin "1") (pinfunction "1_1") (pintype "passive"))
    )
    (net (code "33") (name "Net-(R7-Pad2)") (class "Default")
      (node (ref "R7") (pin "2") (pinfunction "2_2") (pintype "passive"))
      (node (ref "R8") (pin "2") (pinfunction "2_2") (pintype "passive"))
    )
    (net (code "34") (name "unconnected-(IC1-OUT-Pad2)") (class "Default")
      (node (ref "IC1") (pin "2") (pinfunction "OUT_2") (pintype "passive+no_connect"))
    )
    (net (code "35") (name "unconnected-(J2-Pad03)") (class "Default")
      (node (ref "J2") (pin "03") (pinfunction "03_03") (pintype "passive+no_connect"))
    )
    (net (code "36") (name "unconnected-(J2-Pad05)") (class "Default")
      (node (ref "J2") (pin "05") (pinfunction "05_05") (pintype "passive+no_connect"))
    )
    (net (code "37") (name "unconnected-(J2-Pad07)") (class "Default")
      (node (ref "J2") (pin "07") (pinfunction "07_07") (pintype "passive+no_connect"))
    )
    (net (code "38") (name "unconnected-(J2-Pad09)") (class "Default")
      (node (ref "J2") (pin "09") (pinfunction "09_09") (pintype "passive+no_connect"))
    )
    (net (code "39") (name "unconnected-(J2-Pad10)") (class "Default")
      (node (ref "J2") (pin "10") (pinfunction "10_10") (pintype "passive+no_connect"))
    )
    (net (code "40") (name "unconnected-(J2-Pad11)") (class "Default")
      (node (ref "J2") (pin "11") (pinfunction "11_11") (pintype "passive+no_connect"))
    )
    (net (code "41") (name "unconnected-(J2-Pad12)") (class "Default")
      (node (ref "J2") (pin "12") (pinfunction "12_12") (pintype "passive+no_connect"))
    )
    (net (code "42") (name "unconnected-(J2-Pad13)") (class "Default")
      (node (ref "J2") (pin "13") (pinfunction "13_13") (pintype "passive+no_connect"))
    )
    (net (code "43") (name "unconnected-(J2-Pad14)") (class "Default")
      (node (ref "J2") (pin "14") (pinfunction "14_14") (pintype "passive+no_connect"))
    )
    (net (code "44") (name "unconnected-(J2-Pad15)") (class "Default")
      (node (ref "J2") (pin "15") (pinfunction "15_15") (pintype "passive+no_connect"))
    )
    (net (code "45") (name "unconnected-(J2-Pad16)") (class "Default")
      (node (ref "J2") (pin "16") (pinfunction "16_16") (pintype "passive+no_connect"))
    )
    (net (code "46") (name "unconnected-(J2-Pad17)") (class "Default")
      (node (ref "J2") (pin "17") (pinfunction "17_17") (pintype "passive+no_connect"))
    )
    (net (code "47") (name "unconnected-(J2-Pad18)") (class "Default")
      (node (ref "J2") (pin "18") (pinfunction "18_18") (pintype "passive+no_connect"))
    )
    (net (code "48") (name "unconnected-(J2-Pad19)") (class "Default")
      (node (ref "J2") (pin "19") (pinfunction "19_19") (pintype "passive+no_connect"))
    )
    (net (code "49") (name "unconnected-(J2-Pad21)") (class "Default")
      (node (ref "J2") (pin "21") (pinfunction "21_21") (pintype "passive"))
    )
    (net (code "50") (name "unconnected-(J2-Pad23)") (class "Default")
      (node (ref "J2") (pin "23") (pinfunction "23_23") (pintype "passive+no_connect"))
    )
    (net (code "51") (name "unconnected-(J2-Pad24)") (class "Default")
      (node (ref "J2") (pin "24") (pinfunction "24_24") (pintype "passive"))
    )
    (net (code "52") (name "unconnected-(J2-Pad25)") (class "Default")
      (node (ref "J2") (pin "25") (pinfunction "25_25") (pintype "passive+no_connect"))
    )
    (net (code "53") (name "unconnected-(J2-Pad27)") (class "Default")
      (node (ref "J2") (pin "27") (pinfunction "27_27") (pintype "passive+no_connect"))
    )
    (net (code "54") (name "unconnected-(K1-PadNC)") (class "Default")
      (node (ref "K1") (pin "NC") (pinfunction "NC_NC") (pintype "passive"))
    )
    (net (code "55") (name "unconnected-(K2-PadNC)") (class "Default")
      (node (ref "K2") (pin "NC") (pinfunction "NC_NC") (pintype "passive"))
    )
    (net (code "56") (name "unconnected-(T1-Pad2)") (class "Default")
      (node (ref "T1") (pin "2") (pinfunction "2_2") (pintype "passive+no_connect"))
    )
    (net (code "57") (name "unconnected-(T1-Pad3)") (class "Default")
      (node (ref "T1") (pin "3") (pinfunction "3_3") (pintype "passive+no_connect"))
    )
    (net (code "58") (name "unconnected-(T1-Pad4)") (class "Default")
      (node (ref "T1") (pin "4") (pinfunction "4_4") (pintype "passive+no_connect"))
    )
    (net (code "59") (name "unconnected-(T1-Pad8)") (class "Default")
      (node (ref "T1") (pin "8") (pinfunction "8_8") (pintype "passive+no_connect"))
    )
    (net (code "60") (name "unconnected-(T1-Pad9)") (class "Default")
      (node (ref "T1") (pin "9") (pinfunction "9_9") (pintype "passive"))
    )
    (net (code "61") (name "unconnected-(T1-Pad10)") (class "Default")
      (node (ref "T1") (pin "10") (pinfunction "10_10") (pintype "passive"))
    )
  )
)
